# Regulator.net
KiCad netlist of a schematic drawn in Altium Designer
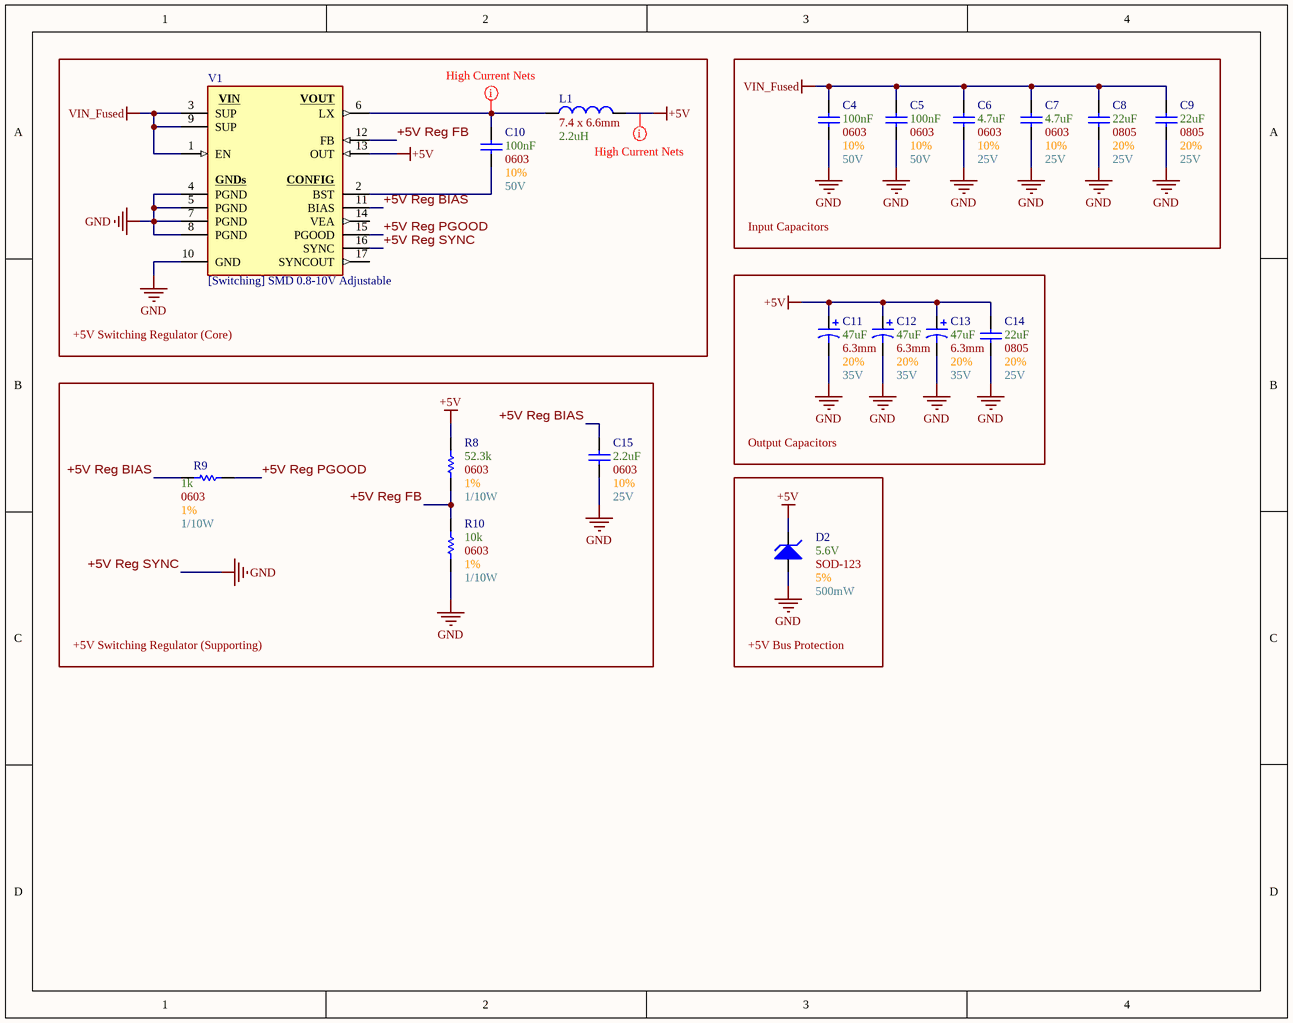
[diagram p0: Regulator.SchDoc]

(export (version "E")
  (design (tool "Eeschema 10.0.6"))
  (components
    (comp (ref "C4")
      (value "[Cap] 0603 0.1uF 10% 50V")
      (footprint "[Cap] SMD 0603")
      (description "CL10B104KB8NNNC")
      (fields
        (field (name "MAX VOLTAGE") "50V")
        (field (name "SIZE PACKAGE") "0603")
        (field (name "TOLERANCE") "10%")
        (field (name "CAPACITANCE") "100nF")
      )
      (libsource (lib "Capacitors") (part "[Cap] 0603 0.1uF 10% 50V"))
    )
    (comp (ref "C5")
      (value "[Cap] 0603 0.1uF 10% 50V")
      (footprint "[Cap] SMD 0603")
      (description "CL10B104KB8NNNC")
      (fields
        (field (name "MAX VOLTAGE") "50V")
        (field (name "SIZE PACKAGE") "0603")
        (field (name "TOLERANCE") "10%")
        (field (name "CAPACITANCE") "100nF")
      )
      (libsource (lib "Capacitors") (part "[Cap] 0603 0.1uF 10% 50V"))
    )
    (comp (ref "C6")
      (value "[Cap] 0603 4.7uF 10% 25V")
      (footprint "[Cap] SMD 0603")
      (description "GRM188R61E475KE11D")
      (fields
        (field (name "MAX VOLTAGE") "25V")
        (field (name "SIZE PACKAGE") "0603")
        (field (name "TOLERANCE") "10%")
        (field (name "CAPACITANCE") "4.7uF")
      )
      (libsource (lib "Capacitors") (part "[Cap] 0603 4.7uF 10% 25V"))
    )
    (comp (ref "C7")
      (value "[Cap] 0603 4.7uF 10% 25V")
      (footprint "[Cap] SMD 0603")
      (description "GRM188R61E475KE11D")
      (fields
        (field (name "MAX VOLTAGE") "25V")
        (field (name "SIZE PACKAGE") "0603")
        (field (name "TOLERANCE") "10%")
        (field (name "CAPACITANCE") "4.7uF")
      )
      (libsource (lib "Capacitors") (part "[Cap] 0603 4.7uF 10% 25V"))
    )
    (comp (ref "C8")
      (value "[Cap] 0805 22uF 20% 25V")
      (footprint "[Cap] SMD 0805")
      (description "CL21A226MAYNNWE")
      (fields
        (field (name "MAX VOLTAGE") "25V")
        (field (name "SIZE PACKAGE") "0805")
        (field (name "TOLERANCE") "20%")
        (field (name "CAPACITANCE") "22uF")
      )
      (libsource (lib "Capacitors") (part "[Cap] 0805 22uF 20% 25V"))
    )
    (comp (ref "C9")
      (value "[Cap] 0805 22uF 20% 25V")
      (footprint "[Cap] SMD 0805")
      (description "CL21A226MAYNNWE")
      (fields
        (field (name "MAX VOLTAGE") "25V")
        (field (name "SIZE PACKAGE") "0805")
        (field (name "TOLERANCE") "20%")
        (field (name "CAPACITANCE") "22uF")
      )
      (libsource (lib "Capacitors") (part "[Cap] 0805 22uF 20% 25V"))
    )
    (comp (ref "C10")
      (value "[Cap] 0603 0.1uF 10% 50V")
      (footprint "[Cap] SMD 0603")
      (description "CL10B104KB8NNNC")
      (fields
        (field (name "MAX VOLTAGE") "50V")
        (field (name "SIZE PACKAGE") "0603")
        (field (name "TOLERANCE") "10%")
        (field (name "CAPACITANCE") "100nF")
      )
      (libsource (lib "Capacitors") (part "[Cap] 0603 0.1uF 10% 50V"))
    )
    (comp (ref "C11")
      (value "[Cap] 6.3mm 47uF 20% 35V")
      (footprint "[Cap] SMD Polarized, 6.3mm")
      (description "UWT1V470MCL1GS")
      (fields
        (field (name "MAX VOLTAGE") "35V")
        (field (name "SIZE PACKAGE") "6.3mm")
        (field (name "TOLERANCE") "20%")
        (field (name "CAPACITANCE") "47uF")
      )
      (libsource (lib "Capacitors") (part "[Cap] 6.3mm 47uF 20% 35V"))
    )
    (comp (ref "C12")
      (value "[Cap] 6.3mm 47uF 20% 35V")
      (footprint "[Cap] SMD Polarized, 6.3mm")
      (description "UWT1V470MCL1GS")
      (fields
        (field (name "MAX VOLTAGE") "35V")
        (field (name "SIZE PACKAGE") "6.3mm")
        (field (name "TOLERANCE") "20%")
        (field (name "CAPACITANCE") "47uF")
      )
      (libsource (lib "Capacitors") (part "[Cap] 6.3mm 47uF 20% 35V"))
    )
    (comp (ref "C13")
      (value "[Cap] 6.3mm 47uF 20% 35V")
      (footprint "[Cap] SMD Polarized, 6.3mm")
      (description "UWT1V470MCL1GS")
      (fields
        (field (name "MAX VOLTAGE") "35V")
        (field (name "SIZE PACKAGE") "6.3mm")
        (field (name "TOLERANCE") "20%")
        (field (name "CAPACITANCE") "47uF")
      )
      (libsource (lib "Capacitors") (part "[Cap] 6.3mm 47uF 20% 35V"))
    )
    (comp (ref "C14")
      (value "[Cap] 0805 22uF 20% 25V")
      (footprint "[Cap] SMD 0805")
      (description "CL21A226MAYNNWE")
      (fields
        (field (name "MAX VOLTAGE") "25V")
        (field (name "SIZE PACKAGE") "0805")
        (field (name "TOLERANCE") "20%")
        (field (name "CAPACITANCE") "22uF")
      )
      (libsource (lib "Capacitors") (part "[Cap] 0805 22uF 20% 25V"))
    )
    (comp (ref "C15")
      (value "[Cap] 0603 2.2uF 10% 25V")
      (footprint "[Cap] SMD 0603")
      (description "GRM188R61E225KA12D")
      (fields
        (field (name "MAX VOLTAGE") "25V")
        (field (name "SIZE PACKAGE") "0603")
        (field (name "TOLERANCE") "10%")
        (field (name "CAPACITANCE") "2.2uF")
      )
      (libsource (lib "Capacitors") (part "[Cap] 0603 2.2uF 10% 25V"))
    )
    (comp (ref "D2")
      (value "SOD-123")
      (footprint "SOD-123")
      (description "CMHZ5232B TR PBFREE")
      (fields
        (field (name "TOLERANCE") "5%")
        (field (name "WATTAGE") "500mW")
        (field (name "OPTIMAL ZENER VOLTAGE") "5.6V")
      )
      (libsource (lib "Diodes") (part "[Zener] SMD 5.6V 1/2W 5%"))
    )
    (comp (ref "L1")
      (value "[2.2uH] SMD Nonstandard 10A")
      (footprint "[Inductor] SMD 7.4 X 6.6 X 3 MM")
      (description "ECS-MPIL0630-2R2MC")
      (fields (field (name "PACKAGE") "7.4 x 6.6mm") (field (name "INDUCTANCE") "2.2uH"))
      (libsource (lib "Inductors") (part "[2.2uH] SMD Nonstandard 10A"))
    )
    (comp (ref "R8")
      (value "[52.3k] SMD 0603 1% 1/10W")
      (footprint "[Res] SMD 0603")
      (description "RC0603FR-0752K3L")
      (fields
        (field (name "WATTAGE") "1/10W")
        (field (name "TOLERANCE") "1%")
        (field (name "RESISTANCE") "52.3k")
        (field (name "SIZE PACKAGE") "0603")
      )
      (libsource (lib "Resistors") (part "[52.3k] SMD 0603 1% 1/10W"))
    )
    (comp (ref "R9")
      (value "[1k] SMD 0603 1% 1/10W")
      (footprint "[Res] SMD 0603")
      (description "RMCF0603FT1K00")
      (fields
        (field (name "WATTAGE") "1/10W")
        (field (name "TOLERANCE") "1%")
        (field (name "RESISTANCE") "1k")
        (field (name "SIZE PACKAGE") "0603")
      )
      (libsource (lib "Resistors") (part "[1k] SMD 0603 1% 1/10W"))
    )
    (comp (ref "R10")
      (value "[10k] SMD 0603 1% 1/8W")
      (footprint "[Res] SMD 0603")
      (description "RMCF0603FT10K0")
      (fields
        (field (name "WATTAGE") "1/10W")
        (field (name "TOLERANCE") "1%")
        (field (name "RESISTANCE") "10k")
        (field (name "SIZE PACKAGE") "0603")
      )
      (libsource (lib "Resistors") (part "[10k] SMD 0603 1% 1/8W"))
    )
    (comp (ref "V1")
      (value "[Switching] SMD 0.8-10V Adjustable")
      (footprint "[Switching] 0.8-10V Adjustable Buck")
      (description "MAX20408AFOF/VY+")
      (libsource (lib "Voltage Regulators") (part "[Switching] SMD 0.8-10V Adjustable"))
    )
  )
  (nets
    (net (code "1") (name "+5V") (class "Default")
      (node (ref "C11") (pin "1") (pinfunction "1_1") (pintype "passive"))
      (node (ref "C12") (pin "1") (pinfunction "1_1") (pintype "passive"))
      (node (ref "C13") (pin "1") (pinfunction "1_1") (pintype "passive"))
      (node (ref "C14") (pin "2") (pinfunction "2_2") (pintype "passive"))
      (node (ref "D2") (pin "1") (pinfunction "K_1") (pintype "passive"))
      (node (ref "L1") (pin "2") (pinfunction "2_2") (pintype "passive"))
      (node (ref "R8") (pin "2") (pinfunction "2_2") (pintype "passive"))
      (node (ref "V1") (pin "13") (pinfunction "OUT_13") (pintype "input"))
    )
    (net (code "2") (name "/+5V Reg BIAS") (class "Default")
      (node (ref "C15") (pin "2") (pinfunction "2_2") (pintype "passive"))
      (node (ref "R9") (pin "1") (pinfunction "1_1") (pintype "passive"))
      (node (ref "V1") (pin "11") (pinfunction "BIAS_11") (pintype "power_in"))
    )
    (net (code "3") (name "/+5V Reg FB") (class "Default")
      (node (ref "R10") (pin "2") (pinfunction "2_2") (pintype "passive"))
      (node (ref "R8") (pin "1") (pinfunction "1_1") (pintype "passive"))
      (node (ref "V1") (pin "12") (pinfunction "FB_12") (pintype "input"))
    )
    (net (code "4") (name "/+5V Reg PGOOD") (class "Default")
      (node (ref "R9") (pin "2") (pinfunction "2_2") (pintype "passive"))
      (node (ref "V1") (pin "15") (pinfunction "PGOOD_15") (pintype "open_collector"))
    )
    (net (code "5") (name "GND") (class "Default")
      (node (ref "C11") (pin "2") (pinfunction "2_2") (pintype "passive"))
      (node (ref "C12") (pin "2") (pinfunction "2_2") (pintype "passive"))
      (node (ref "C13") (pin "2") (pinfunction "2_2") (pintype "passive"))
      (node (ref "C14") (pin "1") (pinfunction "1_1") (pintype "passive"))
      (node (ref "C15") (pin "1") (pinfunction "1_1") (pintype "passive"))
      (node (ref "C4") (pin "1") (pinfunction "1_1") (pintype "passive"))
      (node (ref "C5") (pin "1") (pinfunction "1_1") (pintype "passive"))
      (node (ref "C6") (pin "1") (pinfunction "1_1") (pintype "passive"))
      (node (ref "C7") (pin "1") (pinfunction "1_1") (pintype "passive"))
      (node (ref "C8") (pin "1") (pinfunction "1_1") (pintype "passive"))
      (node (ref "C9") (pin "1") (pinfunction "1_1") (pintype "passive"))
      (node (ref "D2") (pin "2") (pinfunction "A_2") (pintype "passive"))
      (node (ref "R10") (pin "1") (pinfunction "1_1") (pintype "passive"))
      (node (ref "V1") (pin "10") (pinfunction "GND_10") (pintype "power_in"))
      (node (ref "V1") (pin "16") (pinfunction "SYNC_16") (pintype "passive"))
      (node (ref "V1") (pin "4") (pinfunction "PGND_4") (pintype "power_in"))
      (node (ref "V1") (pin "5") (pinfunction "PGND_5") (pintype "power_in"))
      (node (ref "V1") (pin "7") (pinfunction "PGND_7") (pintype "power_in"))
      (node (ref "V1") (pin "8") (pinfunction "PGND_8") (pintype "power_in"))
    )
    (net (code "6") (name "Net-(V1-BST)") (class "Default")
      (node (ref "C10") (pin "1") (pinfunction "1_1") (pintype "passive"))
      (node (ref "V1") (pin "2") (pinfunction "BST_2") (pintype "power_in"))
    )
    (net (code "7") (name "Net-(V1-LX)") (class "Default")
      (node (ref "C10") (pin "2") (pinfunction "2_2") (pintype "passive"))
      (node (ref "L1") (pin "1") (pinfunction "1_1") (pintype "passive"))
      (node (ref "V1") (pin "6") (pinfunction "LX_6") (pintype "output"))
    )
    (net (code "8") (name "VIN_Fused") (class "Default")
      (node (ref "C4") (pin "2") (pinfunction "2_2") (pintype "passive"))
      (node (ref "C5") (pin "2") (pinfunction "2_2") (pintype "passive"))
      (node (ref "C6") (pin "2") (pinfunction "2_2") (pintype "passive"))
      (node (ref "C7") (pin "2") (pinfunction "2_2") (pintype "passive"))
      (node (ref "C8") (pin "2") (pinfunction "2_2") (pintype "passive"))
      (node (ref "C9") (pin "2") (pinfunction "2_2") (pintype "passive"))
      (node (ref "V1") (pin "1") (pinfunction "EN_1") (pintype "input"))
      (node (ref "V1") (pin "3") (pinfunction "SUP_3") (pintype "power_in"))
      (node (ref "V1") (pin "9") (pinfunction "SUP_9") (pintype "power_in"))
    )
    (net (code "9") (name "unconnected-(V1-SYNCOUT-Pad17)") (class "Default")
      (node (ref "V1") (pin "17") (pinfunction "SYNCOUT_17") (pintype "output"))
    )
    (net (code "10") (name "unconnected-(V1-VEA-Pad14)") (class "Default")
      (node (ref "V1") (pin "14") (pinfunction "VEA_14") (pintype "output"))
    )
  )
)
